# Peripheral_MABOS.net
KiCad netlist of a schematic drawn in EAGLE
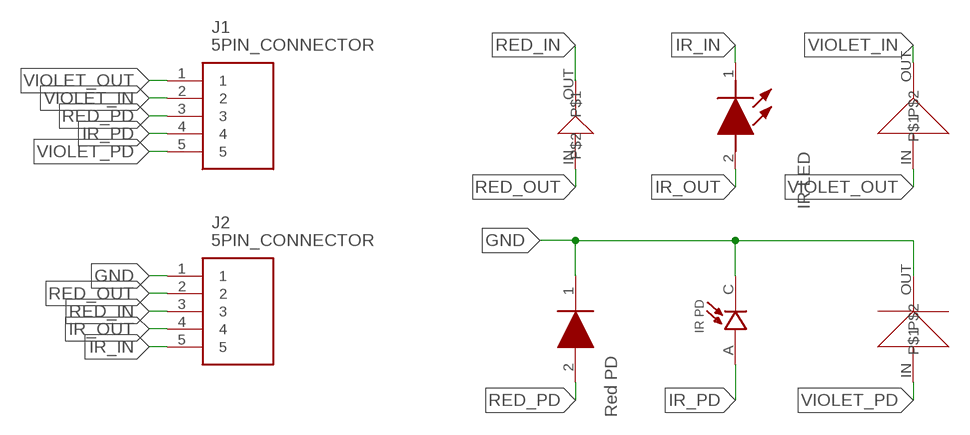
[diagram p0: schematic, sheet 1]

(export (version "E")
  (design (tool "Eeschema 10.0.6"))
  (components
    (comp (ref "D1")
      (value "REDPD")
      (footprint "eagle-import:SFH2713")
      (fields
        (field (name "MANUFACTURER_PART_NUMBER") "SFH 2713")
        (field (name "MOUSER_PART_NUMBER") "720-SFH2713")
      )
      (libsource (lib "eagle-import") (part "REDPD"))
    )
    (comp (ref "D2")
      (value "IRPD")
      (footprint "eagle-import:XDCR_VEMD2023X01")
      (fields (field (name "MF") "Vishay Semiconductor") (field (name "MP") "VEMD2023X01"))
      (libsource (lib "eagle-import") (part "IRPD"))
    )
    (comp (ref "J1")
      (value "5PIN_CONNECTOR")
      (footprint "eagle-import:SHDR5W114P0X419_1X5_2228X658X1")
      (fields
        (field (name "MANUFACTURER_PART_NUMBER") "IPBT-105-H1-T-S-K")
        (field (name "MOUSER_PART_NUMBER") "200-IPBT105H1TSK")
      )
      (libsource (lib "eagle-import") (part "5PIN_CONNECTOR"))
    )
    (comp (ref "J2")
      (value "5PIN_CONNECTOR")
      (footprint "eagle-import:SHDR5W114P0X419_1X5_2228X658X1")
      (fields
        (field (name "MANUFACTURER_PART_NUMBER") "IPBT-105-H1-T-S-K")
        (field (name "MOUSER_PART_NUMBER") "200-IPBT105H1TSK")
      )
      (libsource (lib "eagle-import") (part "5PIN_CONNECTOR"))
    )
    (comp (ref "LED1")
      (value "IRLED")
      (footprint "eagle-import:LEDC3216X180N")
      (fields
        (field (name "MANUFACTURER_PART_NUMBER") "APTD3216F3C-P22")
        (field (name "MOUSER_PART_NUMBER") "604-APTD3216F3C-P22")
      )
      (libsource (lib "eagle-import") (part "IRLED"))
    )
    (comp (ref "U$1")
      (value "REDLED")
      (footprint "eagle-import:REDLED")
      (libsource (lib "eagle-import") (part "REDLED"))
    )
    (comp (ref "U$2")
      (value "UVLED")
      (footprint "eagle-import:UVLED")
      (libsource (lib "eagle-import") (part "UVLED"))
    )
    (comp (ref "U$3")
      (value "UVPD")
      (footprint "eagle-import:UVPD")
      (libsource (lib "eagle-import") (part "UVPD"))
    )
  )
  (nets
    (net (code "1") (name "GND") (class "Default")
      (node (ref "D1") (pin "1") (pinfunction "K_1") (pintype "bidirectional"))
      (node (ref "D2") (pin "C") (pinfunction "C_C") (pintype "passive"))
      (node (ref "J2") (pin "1") (pinfunction "1_1") (pintype "bidirectional"))
      (node (ref "U$3") (pin "OUT") (pinfunction "P$1_OUT") (pintype "output"))
    )
    (net (code "2") (name "IR_IN") (class "Default")
      (node (ref "J2") (pin "5") (pinfunction "5_5") (pintype "bidirectional"))
      (node (ref "LED1") (pin "1") (pinfunction "K_1") (pintype "bidirectional"))
    )
    (net (code "3") (name "IR_OUT") (class "Default")
      (node (ref "J2") (pin "4") (pinfunction "4_4") (pintype "bidirectional"))
      (node (ref "LED1") (pin "2") (pinfunction "A_2") (pintype "bidirectional"))
    )
    (net (code "4") (name "IR_PD") (class "Default")
      (node (ref "D2") (pin "A") (pinfunction "A_A") (pintype "passive"))
      (node (ref "J1") (pin "4") (pinfunction "4_4") (pintype "bidirectional"))
    )
    (net (code "5") (name "RED_IN") (class "Default")
      (node (ref "J2") (pin "3") (pinfunction "3_3") (pintype "bidirectional"))
      (node (ref "U$1") (pin "OUT") (pinfunction "P$2_OUT") (pintype "output"))
    )
    (net (code "6") (name "RED_OUT") (class "Default")
      (node (ref "J2") (pin "2") (pinfunction "2_2") (pintype "bidirectional"))
      (node (ref "U$1") (pin "IN") (pinfunction "P$1_IN") (pintype "input"))
    )
    (net (code "7") (name "RED_PD") (class "Default")
      (node (ref "D1") (pin "2") (pinfunction "A_2") (pintype "bidirectional"))
      (node (ref "J1") (pin "3") (pinfunction "3_3") (pintype "bidirectional"))
    )
    (net (code "8") (name "VIOLET_IN") (class "Default")
      (node (ref "J1") (pin "2") (pinfunction "2_2") (pintype "bidirectional"))
      (node (ref "U$2") (pin "OUT") (pinfunction "P$1_OUT") (pintype "output"))
    )
    (net (code "9") (name "VIOLET_OUT") (class "Default")
      (node (ref "J1") (pin "1") (pinfunction "1_1") (pintype "bidirectional"))
      (node (ref "U$2") (pin "IN") (pinfunction "P$2_IN") (pintype "input"))
    )
    (net (code "10") (name "VIOLET_PD") (class "Default")
      (node (ref "J1") (pin "5") (pinfunction "5_5") (pintype "bidirectional"))
      (node (ref "U$3") (pin "IN") (pinfunction "P$2_IN") (pintype "input"))
    )
  )
)
